# WalkerStalkerv01.net
KiCad netlist of a schematic drawn in EAGLE
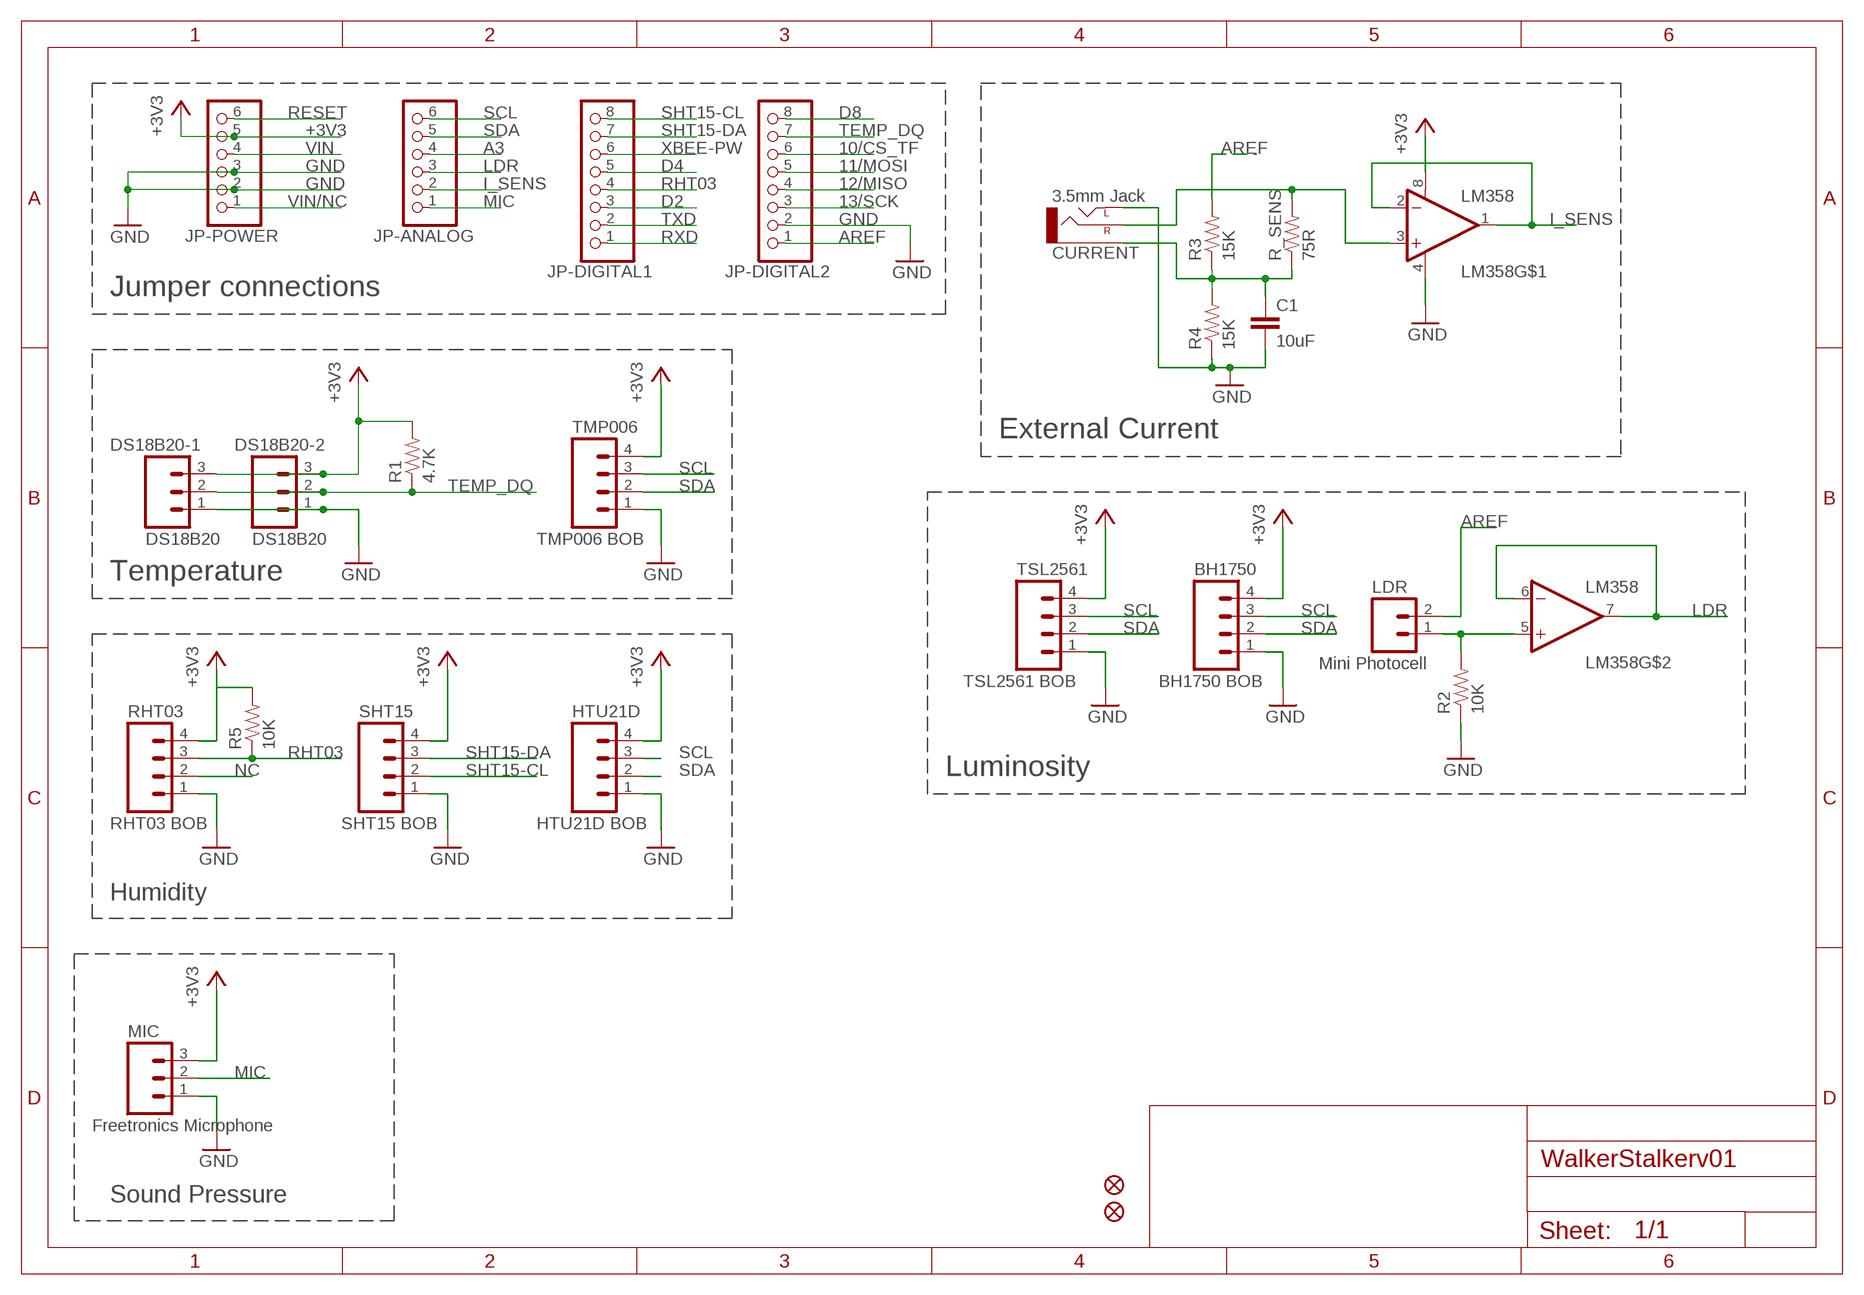
[diagram p0: schematic, sheet 1]

(export (version "E")
  (design (tool "Eeschema 10.0.6"))
  (components
    (comp (ref "BH1750")
      (value "BH1750 BOB")
      (footprint "eagle-import:MOLEX-1X4")
      (libsource (lib "eagle-import") (part "M04POLAR"))
    )
    (comp (ref "C1")
      (value "10uF")
      (footprint "eagle-import:1206")
      (libsource (lib "eagle-import") (part "CAP1206"))
    )
    (comp (ref "CURRENT")
      (value "3.5mm Jack")
      (footprint "eagle-import:AUDIO-JACK")
      (libsource (lib "eagle-import") (part "AUDIO-JACKPTH"))
    )
    (comp (ref "DS18B20-1")
      (value "DS18B20")
      (footprint "eagle-import:MOLEX-1X3")
      (libsource (lib "eagle-import") (part "M03POLAR"))
    )
    (comp (ref "DS18B20-2")
      (value "DS18B20")
      (footprint "eagle-import:MOLEX-1X3")
      (libsource (lib "eagle-import") (part "M03POLAR"))
    )
    (comp (ref "FID1")
      (value "FIDUCIAL1.5X3")
      (footprint "eagle-import:FIDUCIAL-1.5X3")
      (libsource (lib "eagle-import") (part "FIDUCIAL1.5X3"))
    )
    (comp (ref "FID2")
      (value "FIDUCIAL1.5X3")
      (footprint "eagle-import:FIDUCIAL-1.5X3")
      (libsource (lib "eagle-import") (part "FIDUCIAL1.5X3"))
    )
    (comp (ref "HTU21D")
      (value "HTU21D BOB")
      (footprint "eagle-import:MOLEX-1X4")
      (libsource (lib "eagle-import") (part "M04POLAR"))
    )
    (comp (ref "JP-ANALOG")
      (value "PINHD-1X6CB")
      (footprint "eagle-import:1X06-CLEANBIG")
      (libsource (lib "eagle-import") (part "PINHD-1X6CB"))
    )
    (comp (ref "JP-DIGITAL1")
      (value "PINHD-1X8CLEANBIG")
      (footprint "eagle-import:1X08-CLEANBIG")
      (libsource (lib "eagle-import") (part "PINHD-1X8CLEANBIG"))
    )
    (comp (ref "JP-DIGITAL2")
      (value "PINHD-1X8CLEANBIG")
      (footprint "eagle-import:1X08-CLEANBIG")
      (libsource (lib "eagle-import") (part "PINHD-1X8CLEANBIG"))
    )
    (comp (ref "JP-POWER")
      (value "PINHD-1X6CB")
      (footprint "eagle-import:1X06-CLEANBIG")
      (libsource (lib "eagle-import") (part "PINHD-1X6CB"))
    )
    (comp (ref "LDR")
      (value "Mini Photocell")
      (footprint "eagle-import:MOLEX-1X2")
      (libsource (lib "eagle-import") (part "M02POLAR"))
    )
    (comp (ref "LM358")
      (value "LM358")
      (footprint "eagle-import:DIP08")
      (libsource (lib "eagle-import") (part "LM358"))
    )
    (comp (ref "MIC")
      (value "Freetronics Microphone")
      (footprint "eagle-import:MOLEX-1X3")
      (libsource (lib "eagle-import") (part "M03POLAR"))
    )
    (comp (ref "R1")
      (value "4.7K")
      (footprint "eagle-import:1206")
      (libsource (lib "eagle-import") (part "RESISTOR1206"))
    )
    (comp (ref "R2")
      (value "10K")
      (footprint "eagle-import:1206")
      (libsource (lib "eagle-import") (part "RESISTOR1206"))
    )
    (comp (ref "R3")
      (value "15K")
      (footprint "eagle-import:1206")
      (libsource (lib "eagle-import") (part "RESISTOR1206"))
    )
    (comp (ref "R4")
      (value "15K")
      (footprint "eagle-import:1206")
      (libsource (lib "eagle-import") (part "RESISTOR1206"))
    )
    (comp (ref "R5")
      (value "10K")
      (footprint "eagle-import:1206")
      (libsource (lib "eagle-import") (part "RESISTOR1206"))
    )
    (comp (ref "RHT03")
      (value "RHT03 BOB")
      (footprint "eagle-import:MOLEX-1X4")
      (libsource (lib "eagle-import") (part "M04POLAR"))
    )
    (comp (ref "R_SENS")
      (value "75R")
      (footprint "eagle-import:1206")
      (libsource (lib "eagle-import") (part "RESISTOR1206"))
    )
    (comp (ref "SHT15")
      (value "SHT15 BOB")
      (footprint "eagle-import:MOLEX-1X4")
      (libsource (lib "eagle-import") (part "M04POLAR"))
    )
    (comp (ref "TMP006")
      (value "TMP006 BOB")
      (footprint "eagle-import:MOLEX-1X4")
      (libsource (lib "eagle-import") (part "M04POLAR"))
    )
    (comp (ref "TSL2561")
      (value "TSL2561 BOB")
      (footprint "eagle-import:MOLEX-1X4")
      (libsource (lib "eagle-import") (part "M04POLAR"))
    )
  )
  (nets
    (net (code "1") (name "+3V3") (class "Default")
      (node (ref "BH1750") (pin "4") (pinfunction "4_4") (pintype "passive"))
      (node (ref "DS18B20-1") (pin "3") (pinfunction "3_3") (pintype "passive"))
      (node (ref "DS18B20-2") (pin "3") (pinfunction "3_3") (pintype "passive"))
      (node (ref "HTU21D") (pin "4") (pinfunction "4_4") (pintype "passive"))
      (node (ref "JP-POWER") (pin "5") (pinfunction "5_5") (pintype "passive"))
      (node (ref "LM358") (pin "8") (pinfunction "V+_8") (pintype "power_in"))
      (node (ref "MIC") (pin "3") (pinfunction "3_3") (pintype "passive"))
      (node (ref "R1") (pin "2") (pinfunction "2_2") (pintype "passive"))
      (node (ref "R5") (pin "2") (pinfunction "2_2") (pintype "passive"))
      (node (ref "RHT03") (pin "4") (pinfunction "4_4") (pintype "passive"))
      (node (ref "SHT15") (pin "4") (pinfunction "4_4") (pintype "passive"))
      (node (ref "TMP006") (pin "4") (pinfunction "4_4") (pintype "passive"))
      (node (ref "TSL2561") (pin "4") (pinfunction "4_4") (pintype "passive"))
    )
    (net (code "2") (name "/10{slash}CS_TF") (class "Default")
      (node (ref "JP-DIGITAL2") (pin "6") (pinfunction "6_6") (pintype "passive"))
    )
    (net (code "3") (name "/11{slash}MOSI") (class "Default")
      (node (ref "JP-DIGITAL2") (pin "5") (pinfunction "5_5") (pintype "passive"))
    )
    (net (code "4") (name "/12{slash}MISO") (class "Default")
      (node (ref "JP-DIGITAL2") (pin "4") (pinfunction "4_4") (pintype "passive"))
    )
    (net (code "5") (name "/13{slash}SCK") (class "Default")
      (node (ref "JP-DIGITAL2") (pin "3") (pinfunction "3_3") (pintype "passive"))
    )
    (net (code "6") (name "/A3") (class "Default")
      (node (ref "JP-ANALOG") (pin "4") (pinfunction "4_4") (pintype "passive"))
    )
    (net (code "7") (name "/AREF") (class "Default")
      (node (ref "JP-DIGITAL2") (pin "1") (pinfunction "1_1") (pintype "passive"))
      (node (ref "LDR") (pin "2") (pinfunction "2_2") (pintype "passive"))
      (node (ref "R3") (pin "2") (pinfunction "2_2") (pintype "passive"))
    )
    (net (code "8") (name "/D2") (class "Default")
      (node (ref "JP-DIGITAL1") (pin "3") (pinfunction "3_3") (pintype "passive"))
    )
    (net (code "9") (name "/D4") (class "Default")
      (node (ref "JP-DIGITAL1") (pin "5") (pinfunction "5_5") (pintype "passive"))
    )
    (net (code "10") (name "/D8") (class "Default")
      (node (ref "JP-DIGITAL2") (pin "8") (pinfunction "8_8") (pintype "passive"))
    )
    (net (code "11") (name "/I_SENS") (class "Default")
      (node (ref "JP-ANALOG") (pin "2") (pinfunction "2_2") (pintype "passive"))
      (node (ref "LM358") (pin "1") (pinfunction "OUT_1") (pintype "output"))
      (node (ref "LM358") (pin "2") (pinfunction "-IN_2") (pintype "input"))
    )
    (net (code "12") (name "/LDR") (class "Default")
      (node (ref "JP-ANALOG") (pin "3") (pinfunction "3_3") (pintype "passive"))
      (node (ref "LM358") (pin "6") (pinfunction "-IN_6") (pintype "input"))
      (node (ref "LM358") (pin "7") (pinfunction "OUT_7") (pintype "output"))
    )
    (net (code "13") (name "/MIC") (class "Default")
      (node (ref "JP-ANALOG") (pin "1") (pinfunction "1_1") (pintype "passive"))
      (node (ref "MIC") (pin "2") (pinfunction "2_2") (pintype "passive"))
    )
    (net (code "14") (name "/NC") (class "Default")
      (node (ref "RHT03") (pin "2") (pinfunction "2_2") (pintype "passive"))
    )
    (net (code "15") (name "/RESET") (class "Default")
      (node (ref "JP-POWER") (pin "6") (pinfunction "6_6") (pintype "passive"))
    )
    (net (code "16") (name "/RHT03") (class "Default")
      (node (ref "JP-DIGITAL1") (pin "4") (pinfunction "4_4") (pintype "passive"))
      (node (ref "R5") (pin "1") (pinfunction "1_1") (pintype "passive"))
      (node (ref "RHT03") (pin "3") (pinfunction "3_3") (pintype "passive"))
    )
    (net (code "17") (name "/RXD") (class "Default")
      (node (ref "JP-DIGITAL1") (pin "1") (pinfunction "1_1") (pintype "passive"))
    )
    (net (code "18") (name "/SCL") (class "Default")
      (node (ref "BH1750") (pin "3") (pinfunction "3_3") (pintype "passive"))
      (node (ref "HTU21D") (pin "3") (pinfunction "3_3") (pintype "passive"))
      (node (ref "JP-ANALOG") (pin "6") (pinfunction "6_6") (pintype "passive"))
      (node (ref "TMP006") (pin "3") (pinfunction "3_3") (pintype "passive"))
      (node (ref "TSL2561") (pin "3") (pinfunction "3_3") (pintype "passive"))
    )
    (net (code "19") (name "/SDA") (class "Default")
      (node (ref "BH1750") (pin "2") (pinfunction "2_2") (pintype "passive"))
      (node (ref "HTU21D") (pin "2") (pinfunction "2_2") (pintype "passive"))
      (node (ref "JP-ANALOG") (pin "5") (pinfunction "5_5") (pintype "passive"))
      (node (ref "TMP006") (pin "2") (pinfunction "2_2") (pintype "passive"))
      (node (ref "TSL2561") (pin "2") (pinfunction "2_2") (pintype "passive"))
    )
    (net (code "20") (name "/SHT15-CL") (class "Default")
      (node (ref "JP-DIGITAL1") (pin "8") (pinfunction "8_8") (pintype "passive"))
      (node (ref "SHT15") (pin "2") (pinfunction "2_2") (pintype "passive"))
    )
    (net (code "21") (name "/SHT15-DA") (class "Default")
      (node (ref "JP-DIGITAL1") (pin "7") (pinfunction "7_7") (pintype "passive"))
      (node (ref "SHT15") (pin "3") (pinfunction "3_3") (pintype "passive"))
    )
    (net (code "22") (name "/TEMP_DQ") (class "Default")
      (node (ref "DS18B20-1") (pin "2") (pinfunction "2_2") (pintype "passive"))
      (node (ref "DS18B20-2") (pin "2") (pinfunction "2_2") (pintype "passive"))
      (node (ref "JP-DIGITAL2") (pin "7") (pinfunction "7_7") (pintype "passive"))
      (node (ref "R1") (pin "1") (pinfunction "1_1") (pintype "passive"))
    )
    (net (code "23") (name "/TXD") (class "Default")
      (node (ref "JP-DIGITAL1") (pin "2") (pinfunction "2_2") (pintype "passive"))
    )
    (net (code "24") (name "/VIN") (class "Default")
      (node (ref "JP-POWER") (pin "4") (pinfunction "4_4") (pintype "passive"))
    )
    (net (code "25") (name "/VIN{slash}NC") (class "Default")
      (node (ref "JP-POWER") (pin "1") (pinfunction "1_1") (pintype "passive"))
    )
    (net (code "26") (name "/XBEE-PW") (class "Default")
      (node (ref "JP-DIGITAL1") (pin "6") (pinfunction "6_6") (pintype "passive"))
    )
    (net (code "27") (name "GND") (class "Default")
      (node (ref "BH1750") (pin "1") (pinfunction "1_1") (pintype "passive"))
      (node (ref "C1") (pin "2") (pinfunction "2_2") (pintype "passive"))
      (node (ref "CURRENT") (pin "TIP") (pinfunction "LEFT_TIP") (pintype "bidirectional"))
      (node (ref "DS18B20-1") (pin "1") (pinfunction "1_1") (pintype "passive"))
      (node (ref "DS18B20-2") (pin "1") (pinfunction "1_1") (pintype "passive"))
      (node (ref "HTU21D") (pin "1") (pinfunction "1_1") (pintype "passive"))
      (node (ref "JP-DIGITAL2") (pin "2") (pinfunction "2_2") (pintype "passive"))
      (node (ref "JP-POWER") (pin "2") (pinfunction "2_2") (pintype "passive"))
      (node (ref "JP-POWER") (pin "3") (pinfunction "3_3") (pintype "passive"))
      (node (ref "LM358") (pin "4") (pinfunction "V-_4") (pintype "power_in"))
      (node (ref "MIC") (pin "1") (pinfunction "1_1") (pintype "passive"))
      (node (ref "R2") (pin "1") (pinfunction "1_1") (pintype "passive"))
      (node (ref "R4") (pin "1") (pinfunction "1_1") (pintype "passive"))
      (node (ref "RHT03") (pin "1") (pinfunction "1_1") (pintype "passive"))
      (node (ref "SHT15") (pin "1") (pinfunction "1_1") (pintype "passive"))
      (node (ref "TMP006") (pin "1") (pinfunction "1_1") (pintype "passive"))
      (node (ref "TSL2561") (pin "1") (pinfunction "1_1") (pintype "passive"))
    )
    (net (code "28") (name "Net-(C1-Pad1)") (class "Default")
      (node (ref "C1") (pin "1") (pinfunction "1_1") (pintype "passive"))
      (node (ref "CURRENT") (pin "SLEEVE") (pinfunction "SLEEVE_SLEEVE") (pintype "bidirectional"))
      (node (ref "R3") (pin "1") (pinfunction "1_1") (pintype "passive"))
      (node (ref "R4") (pin "2") (pinfunction "2_2") (pintype "passive"))
      (node (ref "R_SENS") (pin "1") (pinfunction "1_1") (pintype "passive"))
    )
    (net (code "29") (name "Net-(CURRENT-RIGHT)") (class "Default")
      (node (ref "CURRENT") (pin "RING") (pinfunction "RIGHT_RING") (pintype "bidirectional"))
      (node (ref "LM358") (pin "3") (pinfunction "+IN_3") (pintype "input"))
      (node (ref "R_SENS") (pin "2") (pinfunction "2_2") (pintype "passive"))
    )
    (net (code "30") (name "Net-(LM358B-+IN)") (class "Default")
      (node (ref "LDR") (pin "1") (pinfunction "1_1") (pintype "passive"))
      (node (ref "LM358") (pin "5") (pinfunction "+IN_5") (pintype "input"))
      (node (ref "R2") (pin "2") (pinfunction "2_2") (pintype "passive"))
    )
  )
)
